# RFTP0805.net
KiCad netlist of a schematic drawn in Altium Designer
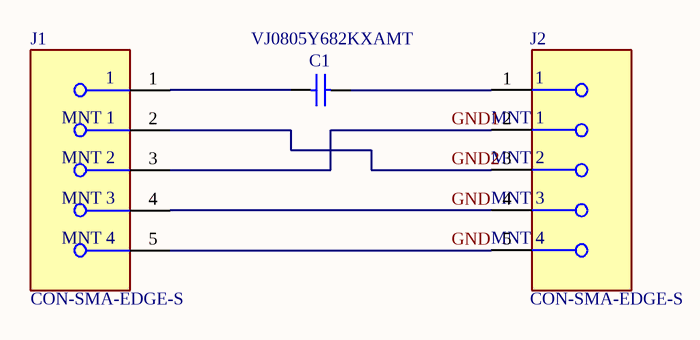
[diagram p0: RFTP0805.SchDoc]

(export (version "E")
  (design (tool "Eeschema 10.0.6"))
  (components
    (comp (ref "C1")
      (value "VJ0805Y682KXAMT")
      (footprint "CAPC2013X145X48ML20T23")
      (fields (field (name "MANUFACTURER") "Vitramon"))
      (libsource (lib "Altium Content Vault") (part "CAP"))
    )
    (comp (ref "J1")
      (value "CON-SMA-EDGE-S")
      (footprint "FP-CON-SMA-EDGE-S-MFG")
      (description "CONN SMA JACK STR EDGE MNT")
      (fields
        (field (name "OCTOPART") "https://octopart.com/con-sma-edge-s-rf+solutions-70967450")
        (field (name "MANUFACTURER") "RF Solutions Ltd.")
      )
      (libsource (lib "Altium Content Vault") (part "a163d97a771fcdd2fd1f1a9264c171f"))
    )
    (comp (ref "J2")
      (value "CON-SMA-EDGE-S")
      (footprint "FP-CON-SMA-EDGE-S-MFG")
      (description "CONN SMA JACK STR EDGE MNT")
      (fields
        (field (name "OCTOPART") "https://octopart.com/con-sma-edge-s-rf+solutions-70967450")
        (field (name "MANUFACTURER") "RF Solutions Ltd.")
      )
      (libsource (lib "") (part "a163d97a771fcdd2fd1f1a9264c171f_1"))
    )
  )
  (nets
    (net (code "1") (name "/GND") (class "Default")
      (node (ref "J1") (pin "4") (pinfunction "MNT_3_4") (pintype "passive"))
      (node (ref "J1") (pin "5") (pinfunction "MNT_4_5") (pintype "passive"))
      (node (ref "J2") (pin "4") (pinfunction "MNT_3_4") (pintype "passive"))
      (node (ref "J2") (pin "5") (pinfunction "MNT_4_5") (pintype "passive"))
    )
    (net (code "2") (name "/GND1") (class "Default")
      (node (ref "J1") (pin "3") (pinfunction "MNT_2_3") (pintype "passive"))
      (node (ref "J2") (pin "2") (pinfunction "MNT_1_2") (pintype "passive"))
    )
    (net (code "3") (name "/GND2") (class "Default")
      (node (ref "J1") (pin "2") (pinfunction "MNT_1_2") (pintype "passive"))
      (node (ref "J2") (pin "3") (pinfunction "MNT_2_3") (pintype "passive"))
    )
    (net (code "4") (name "Net-(C1-Pad1)") (class "Default")
      (node (ref "C1") (pin "1") (pinfunction "1_1") (pintype "passive"))
      (node (ref "J1") (pin "1") (pinfunction "1_1") (pintype "passive"))
    )
    (net (code "5") (name "Net-(C1-Pad2)") (class "Default")
      (node (ref "C1") (pin "2") (pinfunction "2_2") (pintype "passive"))
      (node (ref "J2") (pin "1") (pinfunction "1_1") (pintype "passive"))
    )
  )
)
